# Pyr0-Piezo-FFC-Creality-X-Board.net
KiCad netlist of a schematic drawn in EAGLE
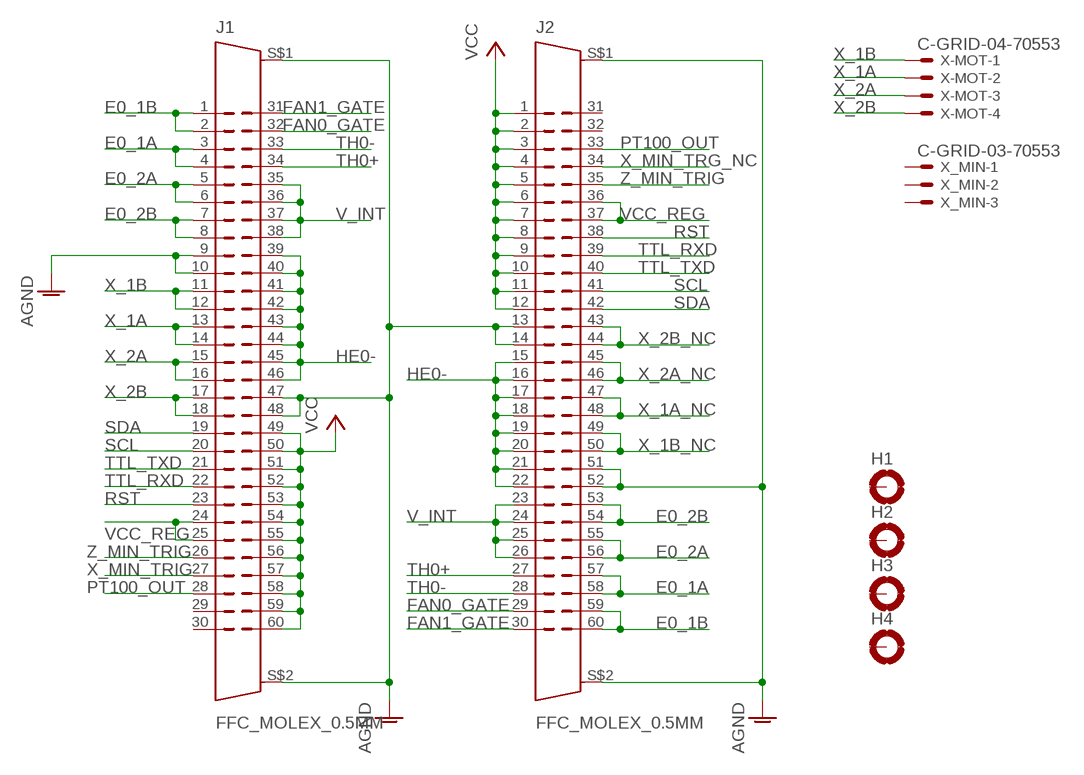
[diagram p0: schematic, sheet 1]

(export (version "E")
  (design (tool "Eeschema 10.0.6"))
  (components
    (comp (ref "H1")
      (value "HOLES_MOUNT-PAD-ROUND3.2")
      (footprint "eagle-import:HOLES_3,2-PAD")
      (libsource (lib "eagle-import") (part "HOLES_MOUNT-PAD-ROUND3.2"))
    )
    (comp (ref "H2")
      (value "HOLES_MOUNT-PAD-ROUND3.2")
      (footprint "eagle-import:HOLES_3,2-PAD")
      (libsource (lib "eagle-import") (part "HOLES_MOUNT-PAD-ROUND3.2"))
    )
    (comp (ref "H3")
      (value "HOLES_MOUNT-PAD-ROUND3.2")
      (footprint "eagle-import:HOLES_3,2-PAD")
      (libsource (lib "eagle-import") (part "HOLES_MOUNT-PAD-ROUND3.2"))
    )
    (comp (ref "H4")
      (value "HOLES_MOUNT-PAD-ROUND3.2")
      (footprint "eagle-import:HOLES_3,2-PAD")
      (libsource (lib "eagle-import") (part "HOLES_MOUNT-PAD-ROUND3.2"))
    )
    (comp (ref "J1")
      (value "FFC_MOLEX_0.5MM")
      (footprint "eagle-import:FFC-60P_0.5_MOLEX_505110-6091")
      (libsource (lib "eagle-import") (part "FFC_MOLEX_0.5MM"))
    )
    (comp (ref "J2")
      (value "FFC_MOLEX_0.5MM")
      (footprint "eagle-import:FFC-60P_0.5_MOLEX_505110-6091")
      (libsource (lib "eagle-import") (part "FFC_MOLEX_0.5MM"))
    )
    (comp (ref "X-MOT")
      (value "C-GRID-04-70553")
      (footprint "eagle-import:70553-04")
      (fields (field (name "MF") "MOLEX"))
      (libsource (lib "eagle-import") (part "C-GRID-04-70553"))
    )
    (comp (ref "X_MIN")
      (value "C-GRID-03-70553")
      (footprint "eagle-import:70553-03")
      (fields (field (name "MF") "MOLEX"))
      (libsource (lib "eagle-import") (part "C-GRID-03-70553"))
    )
  )
  (nets
    (net (code "1") (name "/E0_1A") (class "Default")
      (node (ref "J1") (pin "3") (pinfunction "5_3") (pintype "passive"))
      (node (ref "J1") (pin "4") (pinfunction "6_4") (pintype "passive"))
      (node (ref "J2") (pin "57") (pinfunction "63_57") (pintype "passive"))
      (node (ref "J2") (pin "58") (pinfunction "64_58") (pintype "passive"))
    )
    (net (code "2") (name "/E0_1B") (class "Default")
      (node (ref "J1") (pin "1") (pinfunction "3_1") (pintype "passive"))
      (node (ref "J1") (pin "2") (pinfunction "4_2") (pintype "passive"))
      (node (ref "J2") (pin "59") (pinfunction "65_59") (pintype "passive"))
      (node (ref "J2") (pin "60") (pinfunction "66_60") (pintype "passive"))
    )
    (net (code "3") (name "/E0_2A") (class "Default")
      (node (ref "J1") (pin "5") (pinfunction "7_5") (pintype "passive"))
      (node (ref "J1") (pin "6") (pinfunction "8_6") (pintype "passive"))
      (node (ref "J2") (pin "55") (pinfunction "61_55") (pintype "passive"))
      (node (ref "J2") (pin "56") (pinfunction "62_56") (pintype "passive"))
    )
    (net (code "4") (name "/E0_2B") (class "Default")
      (node (ref "J1") (pin "7") (pinfunction "9_7") (pintype "passive"))
      (node (ref "J1") (pin "8") (pinfunction "10_8") (pintype "passive"))
      (node (ref "J2") (pin "53") (pinfunction "59_53") (pintype "passive"))
      (node (ref "J2") (pin "54") (pinfunction "60_54") (pintype "passive"))
    )
    (net (code "5") (name "/FAN0_GATE") (class "Default")
      (node (ref "J1") (pin "32") (pinfunction "38_32") (pintype "passive"))
      (node (ref "J2") (pin "29") (pinfunction "31_29") (pintype "passive"))
    )
    (net (code "6") (name "/FAN1_GATE") (class "Default")
      (node (ref "J1") (pin "31") (pinfunction "37_31") (pintype "passive"))
      (node (ref "J2") (pin "30") (pinfunction "32_30") (pintype "passive"))
    )
    (net (code "7") (name "/HE0-") (class "Default")
      (node (ref "J1") (pin "39") (pinfunction "45_39") (pintype "passive"))
      (node (ref "J1") (pin "40") (pinfunction "46_40") (pintype "passive"))
      (node (ref "J1") (pin "41") (pinfunction "47_41") (pintype "passive"))
      (node (ref "J1") (pin "42") (pinfunction "48_42") (pintype "passive"))
      (node (ref "J1") (pin "43") (pinfunction "49_43") (pintype "passive"))
      (node (ref "J1") (pin "44") (pinfunction "50_44") (pintype "passive"))
      (node (ref "J1") (pin "45") (pinfunction "51_45") (pintype "passive"))
      (node (ref "J1") (pin "46") (pinfunction "52_46") (pintype "passive"))
      (node (ref "J2") (pin "15") (pinfunction "17_15") (pintype "passive"))
      (node (ref "J2") (pin "16") (pinfunction "18_16") (pintype "passive"))
      (node (ref "J2") (pin "17") (pinfunction "19_17") (pintype "passive"))
      (node (ref "J2") (pin "18") (pinfunction "20_18") (pintype "passive"))
      (node (ref "J2") (pin "19") (pinfunction "21_19") (pintype "passive"))
      (node (ref "J2") (pin "20") (pinfunction "22_20") (pintype "passive"))
      (node (ref "J2") (pin "21") (pinfunction "23_21") (pintype "passive"))
      (node (ref "J2") (pin "22") (pinfunction "24_22") (pintype "passive"))
    )
    (net (code "8") (name "/PT100_OUT") (class "Default")
      (node (ref "J1") (pin "28") (pinfunction "30_28") (pintype "passive"))
      (node (ref "J2") (pin "33") (pinfunction "39_33") (pintype "passive"))
    )
    (net (code "9") (name "/RST") (class "Default")
      (node (ref "J1") (pin "23") (pinfunction "25_23") (pintype "passive"))
      (node (ref "J2") (pin "38") (pinfunction "44_38") (pintype "passive"))
    )
    (net (code "10") (name "/SCL") (class "Default")
      (node (ref "J1") (pin "20") (pinfunction "22_20") (pintype "passive"))
      (node (ref "J2") (pin "41") (pinfunction "47_41") (pintype "passive"))
    )
    (net (code "11") (name "/SDA") (class "Default")
      (node (ref "J1") (pin "19") (pinfunction "21_19") (pintype "passive"))
      (node (ref "J2") (pin "42") (pinfunction "48_42") (pintype "passive"))
    )
    (net (code "12") (name "/TH0+") (class "Default")
      (node (ref "J1") (pin "34") (pinfunction "40_34") (pintype "passive"))
      (node (ref "J2") (pin "27") (pinfunction "29_27") (pintype "passive"))
    )
    (net (code "13") (name "/TH0-") (class "Default")
      (node (ref "J1") (pin "33") (pinfunction "39_33") (pintype "passive"))
      (node (ref "J2") (pin "28") (pinfunction "30_28") (pintype "passive"))
    )
    (net (code "14") (name "/TTL_RXD") (class "Default")
      (node (ref "J1") (pin "22") (pinfunction "24_22") (pintype "passive"))
      (node (ref "J2") (pin "39") (pinfunction "45_39") (pintype "passive"))
    )
    (net (code "15") (name "/TTL_TXD") (class "Default")
      (node (ref "J1") (pin "21") (pinfunction "23_21") (pintype "passive"))
      (node (ref "J2") (pin "40") (pinfunction "46_40") (pintype "passive"))
    )
    (net (code "16") (name "/VCC_REG") (class "Default")
      (node (ref "J1") (pin "24") (pinfunction "26_24") (pintype "passive"))
      (node (ref "J1") (pin "25") (pinfunction "27_25") (pintype "passive"))
      (node (ref "J2") (pin "36") (pinfunction "42_36") (pintype "passive"))
      (node (ref "J2") (pin "37") (pinfunction "43_37") (pintype "passive"))
    )
    (net (code "17") (name "/V_INT") (class "Default")
      (node (ref "J1") (pin "35") (pinfunction "41_35") (pintype "passive"))
      (node (ref "J1") (pin "36") (pinfunction "42_36") (pintype "passive"))
      (node (ref "J1") (pin "37") (pinfunction "43_37") (pintype "passive"))
      (node (ref "J1") (pin "38") (pinfunction "44_38") (pintype "passive"))
      (node (ref "J2") (pin "23") (pinfunction "25_23") (pintype "passive"))
      (node (ref "J2") (pin "24") (pinfunction "26_24") (pintype "passive"))
      (node (ref "J2") (pin "25") (pinfunction "27_25") (pintype "passive"))
      (node (ref "J2") (pin "26") (pinfunction "28_26") (pintype "passive"))
    )
    (net (code "18") (name "/X_1A") (class "Default")
      (node (ref "J1") (pin "13") (pinfunction "15_13") (pintype "passive"))
      (node (ref "J1") (pin "14") (pinfunction "16_14") (pintype "passive"))
      (node (ref "X-MOT") (pin "2") (pinfunction "S_2") (pintype "passive"))
    )
    (net (code "19") (name "/X_1A_NC") (class "Default")
      (node (ref "J2") (pin "47") (pinfunction "53_47") (pintype "passive"))
      (node (ref "J2") (pin "48") (pinfunction "54_48") (pintype "passive"))
    )
    (net (code "20") (name "/X_1B") (class "Default")
      (node (ref "J1") (pin "11") (pinfunction "13_11") (pintype "passive"))
      (node (ref "J1") (pin "12") (pinfunction "14_12") (pintype "passive"))
      (node (ref "X-MOT") (pin "1") (pinfunction "S_1") (pintype "passive"))
    )
    (net (code "21") (name "/X_1B_NC") (class "Default")
      (node (ref "J2") (pin "49") (pinfunction "55_49") (pintype "passive"))
      (node (ref "J2") (pin "50") (pinfunction "56_50") (pintype "passive"))
    )
    (net (code "22") (name "/X_2A") (class "Default")
      (node (ref "J1") (pin "15") (pinfunction "17_15") (pintype "passive"))
      (node (ref "J1") (pin "16") (pinfunction "18_16") (pintype "passive"))
      (node (ref "X-MOT") (pin "3") (pinfunction "S_3") (pintype "passive"))
    )
    (net (code "23") (name "/X_2A_NC") (class "Default")
      (node (ref "J2") (pin "45") (pinfunction "51_45") (pintype "passive"))
      (node (ref "J2") (pin "46") (pinfunction "52_46") (pintype "passive"))
    )
    (net (code "24") (name "/X_2B") (class "Default")
      (node (ref "J1") (pin "17") (pinfunction "19_17") (pintype "passive"))
      (node (ref "J1") (pin "18") (pinfunction "20_18") (pintype "passive"))
      (node (ref "X-MOT") (pin "4") (pinfunction "S_4") (pintype "passive"))
    )
    (net (code "25") (name "/X_2B_NC") (class "Default")
      (node (ref "J2") (pin "43") (pinfunction "49_43") (pintype "passive"))
      (node (ref "J2") (pin "44") (pinfunction "50_44") (pintype "passive"))
    )
    (net (code "26") (name "/X_MIN_TRG_NC") (class "Default")
      (node (ref "J2") (pin "34") (pinfunction "40_34") (pintype "passive"))
    )
    (net (code "27") (name "/X_MIN_TRIG") (class "Default")
      (node (ref "J1") (pin "27") (pinfunction "29_27") (pintype "passive"))
    )
    (net (code "28") (name "/Z_MIN_TRIG") (class "Default")
      (node (ref "J1") (pin "26") (pinfunction "28_26") (pintype "passive"))
      (node (ref "J2") (pin "35") (pinfunction "41_35") (pintype "passive"))
    )
    (net (code "29") (name "AGND") (class "Default")
      (node (ref "J1") (pin "10") (pinfunction "12_10") (pintype "passive"))
      (node (ref "J1") (pin "47") (pinfunction "53_47") (pintype "passive"))
      (node (ref "J1") (pin "48") (pinfunction "54_48") (pintype "passive"))
      (node (ref "J1") (pin "9") (pinfunction "11_9") (pintype "passive"))
      (node (ref "J1") (pin "S$1") (pinfunction "S_S$1") (pintype "passive"))
      (node (ref "J1") (pin "S$2") (pinfunction "S_S$2") (pintype "passive"))
      (node (ref "J2") (pin "13") (pinfunction "15_13") (pintype "passive"))
      (node (ref "J2") (pin "14") (pinfunction "16_14") (pintype "passive"))
      (node (ref "J2") (pin "51") (pinfunction "57_51") (pintype "passive"))
      (node (ref "J2") (pin "52") (pinfunction "58_52") (pintype "passive"))
      (node (ref "J2") (pin "S$1") (pinfunction "S_S$1") (pintype "passive"))
      (node (ref "J2") (pin "S$2") (pinfunction "S_S$2") (pintype "passive"))
    )
    (net (code "30") (name "VCC") (class "Default")
      (node (ref "J1") (pin "49") (pinfunction "55_49") (pintype "passive"))
      (node (ref "J1") (pin "50") (pinfunction "56_50") (pintype "passive"))
      (node (ref "J1") (pin "51") (pinfunction "57_51") (pintype "passive"))
      (node (ref "J1") (pin "52") (pinfunction "58_52") (pintype "passive"))
      (node (ref "J1") (pin "53") (pinfunction "59_53") (pintype "passive"))
      (node (ref "J1") (pin "54") (pinfunction "60_54") (pintype "passive"))
      (node (ref "J1") (pin "55") (pinfunction "61_55") (pintype "passive"))
      (node (ref "J1") (pin "56") (pinfunction "62_56") (pintype "passive"))
      (node (ref "J1") (pin "57") (pinfunction "63_57") (pintype "passive"))
      (node (ref "J1") (pin "58") (pinfunction "64_58") (pintype "passive"))
      (node (ref "J1") (pin "59") (pinfunction "65_59") (pintype "passive"))
      (node (ref "J1") (pin "60") (pinfunction "66_60") (pintype "passive"))
      (node (ref "J2") (pin "1") (pinfunction "3_1") (pintype "passive"))
      (node (ref "J2") (pin "10") (pinfunction "12_10") (pintype "passive"))
      (node (ref "J2") (pin "11") (pinfunction "13_11") (pintype "passive"))
      (node (ref "J2") (pin "12") (pinfunction "14_12") (pintype "passive"))
      (node (ref "J2") (pin "2") (pinfunction "4_2") (pintype "passive"))
      (node (ref "J2") (pin "3") (pinfunction "5_3") (pintype "passive"))
      (node (ref "J2") (pin "4") (pinfunction "6_4") (pintype "passive"))
      (node (ref "J2") (pin "5") (pinfunction "7_5") (pintype "passive"))
      (node (ref "J2") (pin "6") (pinfunction "8_6") (pintype "passive"))
      (node (ref "J2") (pin "7") (pinfunction "9_7") (pintype "passive"))
      (node (ref "J2") (pin "8") (pinfunction "10_8") (pintype "passive"))
      (node (ref "J2") (pin "9") (pinfunction "11_9") (pintype "passive"))
    )
    (net (code "31") (name "unconnected-(H1-MOUNT-PadB3,2)") (class "Default")
      (node (ref "H1") (pin "B3,2") (pinfunction "MOUNT_B3,2") (pintype "passive"))
    )
    (net (code "32") (name "unconnected-(H2-MOUNT-PadB3,2)") (class "Default")
      (node (ref "H2") (pin "B3,2") (pinfunction "MOUNT_B3,2") (pintype "passive"))
    )
    (net (code "33") (name "unconnected-(H3-MOUNT-PadB3,2)") (class "Default")
      (node (ref "H3") (pin "B3,2") (pinfunction "MOUNT_B3,2") (pintype "passive"))
    )
    (net (code "34") (name "unconnected-(H4-MOUNT-PadB3,2)") (class "Default")
      (node (ref "H4") (pin "B3,2") (pinfunction "MOUNT_B3,2") (pintype "passive"))
    )
    (net (code "35") (name "unconnected-(J1-31-Pad29)") (class "Default")
      (node (ref "J1") (pin "29") (pinfunction "31_29") (pintype "passive"))
    )
    (net (code "36") (name "unconnected-(J1-32-Pad30)") (class "Default")
      (node (ref "J1") (pin "30") (pinfunction "32_30") (pintype "passive"))
    )
    (net (code "37") (name "unconnected-(J2-37-Pad31)") (class "Default")
      (node (ref "J2") (pin "31") (pinfunction "37_31") (pintype "passive"))
    )
    (net (code "38") (name "unconnected-(J2-38-Pad32)") (class "Default")
      (node (ref "J2") (pin "32") (pinfunction "38_32") (pintype "passive"))
    )
    (net (code "39") (name "unconnected-(X_MINA-S-Pad1)") (class "Default")
      (node (ref "X_MIN") (pin "1") (pinfunction "S_1") (pintype "passive"))
    )
    (net (code "40") (name "unconnected-(X_MINB-S-Pad2)") (class "Default")
      (node (ref "X_MIN") (pin "2") (pinfunction "S_2") (pintype "passive"))
    )
    (net (code "41") (name "unconnected-(X_MINC-S-Pad3)") (class "Default")
      (node (ref "X_MIN") (pin "3") (pinfunction "S_3") (pintype "passive"))
    )
  )
)
